# Sprite_Sail_2_Layer.net
KiCad netlist of a schematic drawn in EAGLE
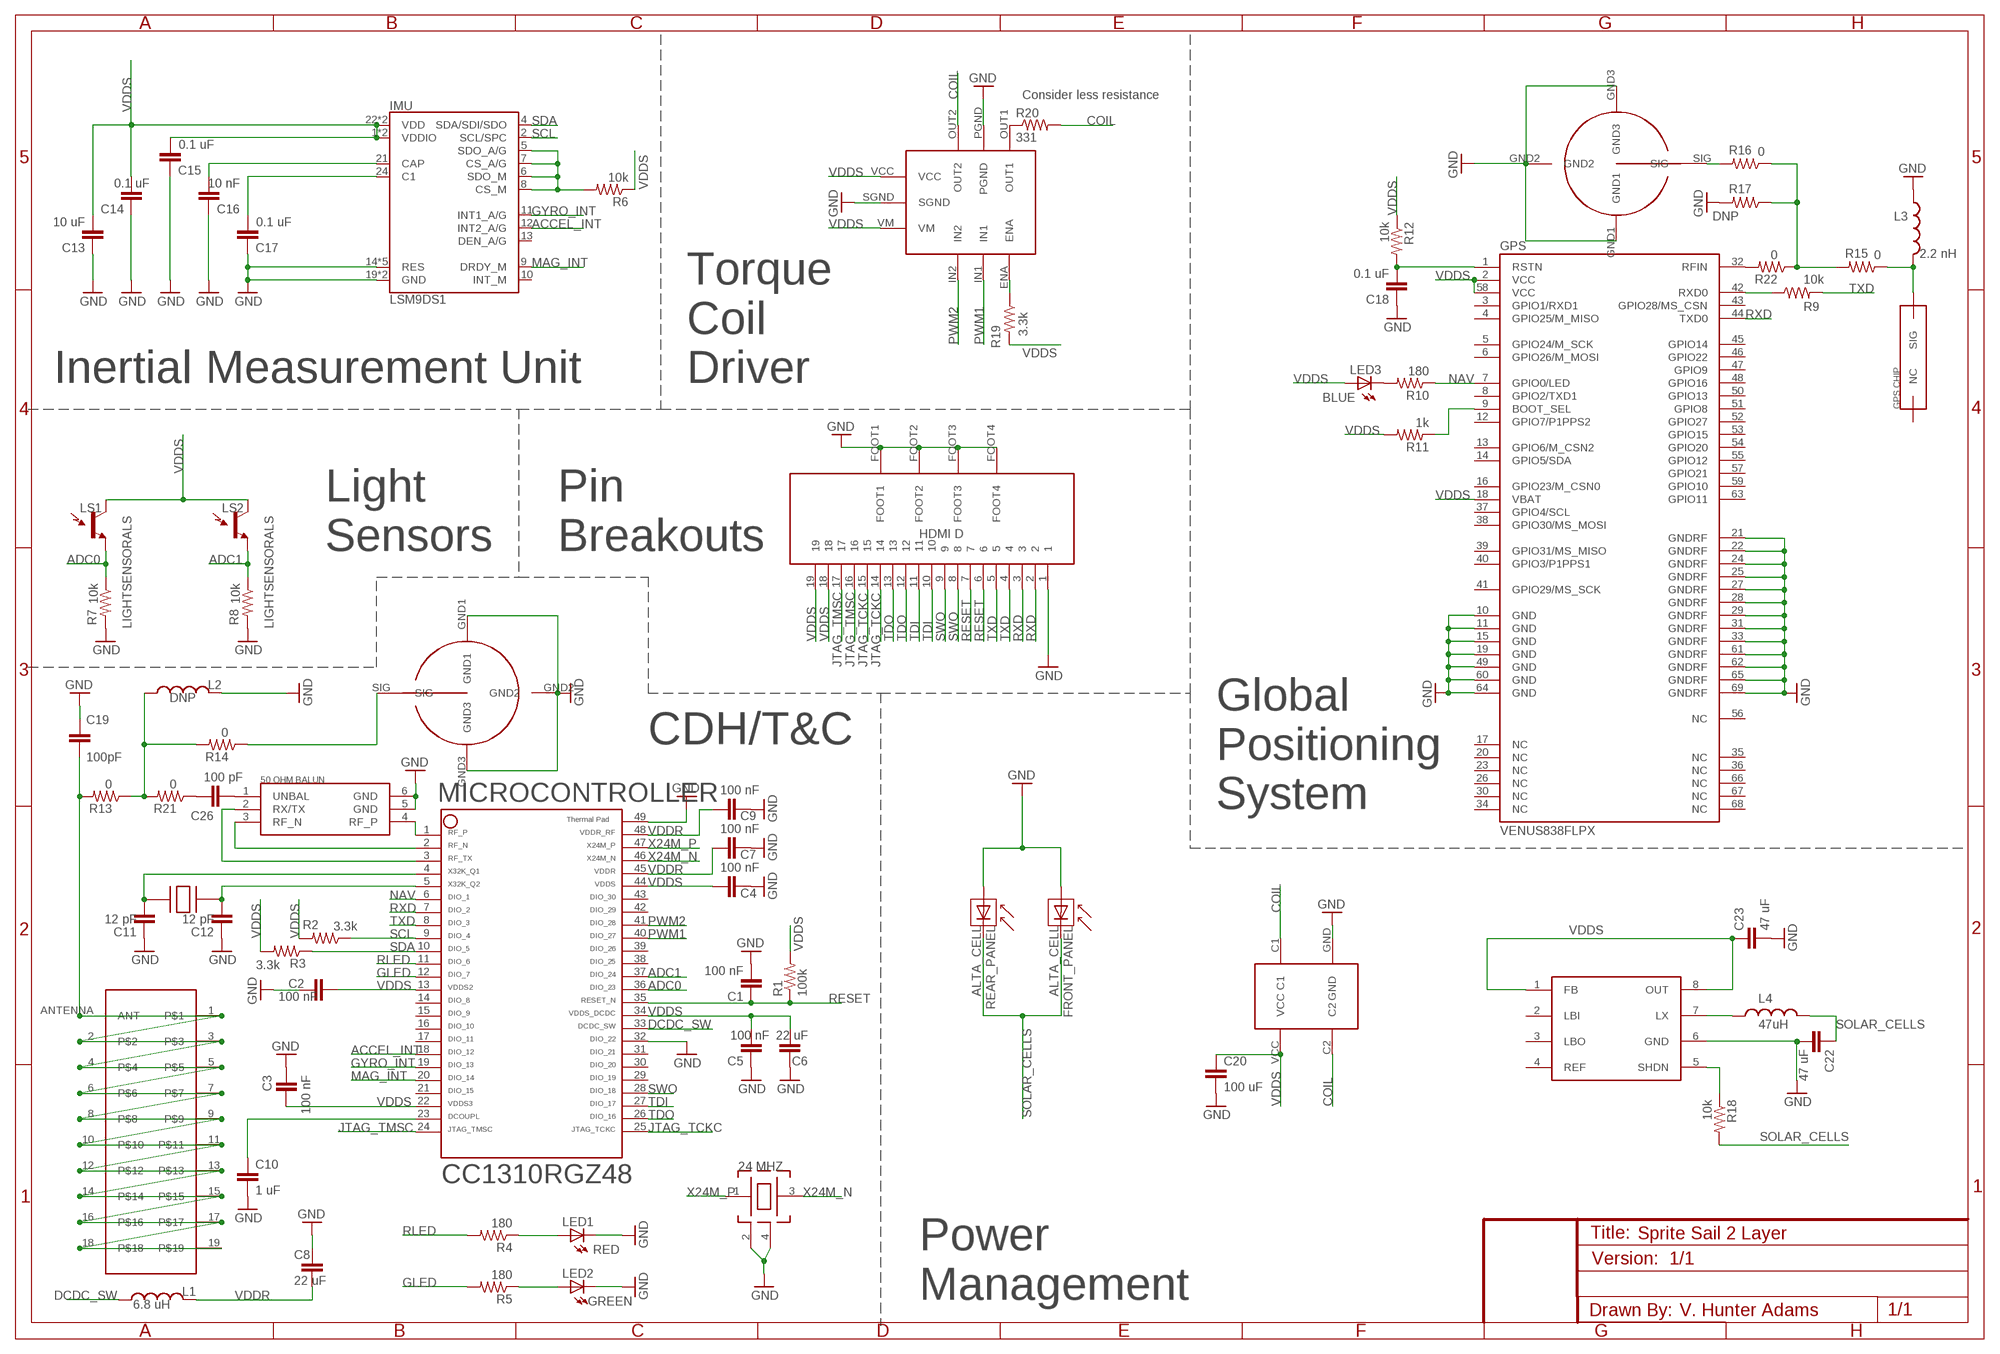
[diagram p0: schematic, sheet 1]

(export (version "E")
  (design (tool "Eeschema 10.0.6"))
  (components
    (comp (ref "32.768")
      (value "FC-135")
      (footprint "eagle-import:FC-135")
      (libsource (lib "eagle-import") (part "FC-135"))
    )
    (comp (ref "BALUN")
      (value "JOHANSON_BALUN")
      (footprint "eagle-import:JOHANSON_BALUN")
      (libsource (lib "eagle-import") (part "JOHANSON_BALUN"))
    )
    (comp (ref "C1")
      (value "100 nF")
      (footprint "eagle-import:0402-CAP")
      (libsource (lib "eagle-import") (part "CAP0402-CAP"))
    )
    (comp (ref "C2")
      (value "100 nF")
      (footprint "eagle-import:0402-CAP")
      (libsource (lib "eagle-import") (part "CAP0402-CAP"))
    )
    (comp (ref "C3")
      (value "100 nF")
      (footprint "eagle-import:0402-CAP")
      (libsource (lib "eagle-import") (part "CAP0402-CAP"))
    )
    (comp (ref "C4")
      (value "100 nF")
      (footprint "eagle-import:0402-CAP")
      (libsource (lib "eagle-import") (part "CAP0402-CAP"))
    )
    (comp (ref "C5")
      (value "100 nF")
      (footprint "eagle-import:0402-CAP")
      (libsource (lib "eagle-import") (part "CAP0402-CAP"))
    )
    (comp (ref "C6")
      (value "22 uF")
      (footprint "eagle-import:0402-CAP")
      (libsource (lib "eagle-import") (part "CAP0402-CAP"))
    )
    (comp (ref "C7")
      (value "100 nF")
      (footprint "eagle-import:0402-CAP")
      (libsource (lib "eagle-import") (part "CAP0402-CAP"))
    )
    (comp (ref "C8")
      (value "22 uF")
      (footprint "eagle-import:0402-CAP")
      (libsource (lib "eagle-import") (part "CAP0402-CAP"))
    )
    (comp (ref "C9")
      (value "100 nF")
      (footprint "eagle-import:0402-CAP")
      (libsource (lib "eagle-import") (part "CAP0402-CAP"))
    )
    (comp (ref "C10")
      (value "1 uF")
      (footprint "eagle-import:0402-CAP")
      (libsource (lib "eagle-import") (part "CAP0402-CAP"))
    )
    (comp (ref "C11")
      (value "12 pF")
      (footprint "eagle-import:0402-CAP")
      (libsource (lib "eagle-import") (part "CAP0402-CAP"))
    )
    (comp (ref "C12")
      (value "12 pF")
      (footprint "eagle-import:0402-CAP")
      (libsource (lib "eagle-import") (part "CAP0402-CAP"))
    )
    (comp (ref "C13")
      (value "10 uF")
      (footprint "eagle-import:0402-CAP")
      (libsource (lib "eagle-import") (part "CAP0402-CAP"))
    )
    (comp (ref "C14")
      (value "0.1 uF")
      (footprint "eagle-import:0402-CAP")
      (libsource (lib "eagle-import") (part "CAP0402-CAP"))
    )
    (comp (ref "C15")
      (value "0.1 uF")
      (footprint "eagle-import:0402-CAP")
      (libsource (lib "eagle-import") (part "CAP0402-CAP"))
    )
    (comp (ref "C16")
      (value "10 nF")
      (footprint "eagle-import:0402-CAP")
      (libsource (lib "eagle-import") (part "CAP0402-CAP"))
    )
    (comp (ref "C17")
      (value "0.1 uF")
      (footprint "eagle-import:0402-CAP")
      (libsource (lib "eagle-import") (part "CAP0402-CAP"))
    )
    (comp (ref "C18")
      (value "0.1 uF")
      (footprint "eagle-import:0402-CAP")
      (libsource (lib "eagle-import") (part "CAP0402-CAP"))
    )
    (comp (ref "C19")
      (value "100pF")
      (footprint "eagle-import:0603-CAP")
      (libsource (lib "eagle-import") (part "CAP0603-CAP"))
    )
    (comp (ref "C20")
      (value "100 uF")
      (footprint "eagle-import:0805")
      (libsource (lib "eagle-import") (part "CAP0805"))
    )
    (comp (ref "C22")
      (value "47 uF")
      (footprint "eagle-import:0805")
      (libsource (lib "eagle-import") (part "CAP0805"))
    )
    (comp (ref "C23")
      (value "47 uF")
      (footprint "eagle-import:0805")
      (libsource (lib "eagle-import") (part "CAP0805"))
    )
    (comp (ref "C26")
      (value "100 pF")
      (footprint "eagle-import:0402-CAP")
      (libsource (lib "eagle-import") (part "CAP0402-CAP"))
    )
    (comp (ref "FRONT_PANEL")
      (value "ALTA_CELL")
      (footprint "eagle-import:ALTA_CELL")
      (libsource (lib "eagle-import") (part "ALTA_CELL"))
    )
    (comp (ref "GPS")
      (value "VENUS838FLPX")
      (footprint "eagle-import:VENUS838FLPX")
      (libsource (lib "eagle-import") (part "VENUS838FLPX"))
    )
    (comp (ref "IMU")
      (value "LSM9DS1")
      (footprint "eagle-import:LGA24-8X4")
      (libsource (lib "eagle-import") (part "LSM9DS1"))
    )
    (comp (ref "L1")
      (value "6.8 uH")
      (footprint "eagle-import:0603")
      (libsource (lib "eagle-import") (part "INDUCTOR0603"))
    )
    (comp (ref "L2")
      (value "DNP")
      (footprint "eagle-import:0603")
      (libsource (lib "eagle-import") (part "INDUCTOR0603"))
    )
    (comp (ref "L3")
      (value "2.2 nH")
      (footprint "eagle-import:0603")
      (libsource (lib "eagle-import") (part "INDUCTOR0603"))
    )
    (comp (ref "L4")
      (value "47uH")
      (footprint "eagle-import:0603")
      (libsource (lib "eagle-import") (part "INDUCTOR0603"))
    )
    (comp (ref "LED1")
      (value "RED")
      (footprint "eagle-import:LED-0603")
      (libsource (lib "eagle-import") (part "LED0603"))
    )
    (comp (ref "LED2")
      (value "GREEN")
      (footprint "eagle-import:LED-0603")
      (libsource (lib "eagle-import") (part "LED0603"))
    )
    (comp (ref "LED3")
      (value "BLUE")
      (footprint "eagle-import:LED-0603")
      (libsource (lib "eagle-import") (part "LED0603"))
    )
    (comp (ref "LS1")
      (value "LIGHTSENSORALS")
      (footprint "eagle-import:ALS-PT19")
      (libsource (lib "eagle-import") (part "LIGHTSENSORALS"))
    )
    (comp (ref "LS2")
      (value "LIGHTSENSORALS")
      (footprint "eagle-import:ALS-PT19")
      (libsource (lib "eagle-import") (part "LIGHTSENSORALS"))
    )
    (comp (ref "MICROCONTROLLER")
      (value "CC1310")
      (footprint "eagle-import:CC1310")
      (libsource (lib "eagle-import") (part "CC1310"))
    )
    (comp (ref "R1")
      (value "100k")
      (footprint "eagle-import:0402-RES")
      (libsource (lib "eagle-import") (part "RESISTOR0402-RES"))
    )
    (comp (ref "R2")
      (value "3.3k")
      (footprint "eagle-import:0402-RES")
      (libsource (lib "eagle-import") (part "RESISTOR0402-RES"))
    )
    (comp (ref "R3")
      (value "3.3k")
      (footprint "eagle-import:0402-RES")
      (libsource (lib "eagle-import") (part "RESISTOR0402-RES"))
    )
    (comp (ref "R4")
      (value "180")
      (footprint "eagle-import:0402-RES")
      (libsource (lib "eagle-import") (part "RESISTOR0402-RES"))
    )
    (comp (ref "R5")
      (value "180")
      (footprint "eagle-import:0402-RES")
      (libsource (lib "eagle-import") (part "RESISTOR0402-RES"))
    )
    (comp (ref "R6")
      (value "10k")
      (footprint "eagle-import:0402-RES")
      (libsource (lib "eagle-import") (part "RESISTOR0402-RES"))
    )
    (comp (ref "R7")
      (value "10k")
      (footprint "eagle-import:0402-RES")
      (libsource (lib "eagle-import") (part "RESISTOR0402-RES"))
    )
    (comp (ref "R8")
      (value "10k")
      (footprint "eagle-import:0402-RES")
      (libsource (lib "eagle-import") (part "RESISTOR0402-RES"))
    )
    (comp (ref "R9")
      (value "10k")
      (footprint "eagle-import:0402-RES")
      (libsource (lib "eagle-import") (part "RESISTOR0402-RES"))
    )
    (comp (ref "R10")
      (value "180")
      (footprint "eagle-import:0402-RES")
      (libsource (lib "eagle-import") (part "RESISTOR0402-RES"))
    )
    (comp (ref "R11")
      (value "1k")
      (footprint "eagle-import:0402-RES")
      (libsource (lib "eagle-import") (part "RESISTOR0402-RES"))
    )
    (comp (ref "R12")
      (value "10k")
      (footprint "eagle-import:0402-RES")
      (libsource (lib "eagle-import") (part "RESISTOR0402-RES"))
    )
    (comp (ref "R13")
      (value "0")
      (footprint "eagle-import:0603-RES")
      (libsource (lib "eagle-import") (part "RESISTOR0603-RES"))
    )
    (comp (ref "R14")
      (value "0")
      (footprint "eagle-import:0603-RES")
      (libsource (lib "eagle-import") (part "RESISTOR0603-RES"))
    )
    (comp (ref "R15")
      (value "0")
      (footprint "eagle-import:0603-RES")
      (libsource (lib "eagle-import") (part "RESISTOR0603-RES"))
    )
    (comp (ref "R16")
      (value "0")
      (footprint "eagle-import:0603-RES")
      (libsource (lib "eagle-import") (part "RESISTOR0603-RES"))
    )
    (comp (ref "R17")
      (value "DNP")
      (footprint "eagle-import:0603-RES")
      (libsource (lib "eagle-import") (part "RESISTOR0603-RES"))
    )
    (comp (ref "R18")
      (value "10k")
      (footprint "eagle-import:0402-RES")
      (libsource (lib "eagle-import") (part "RESISTOR0402-RES"))
    )
    (comp (ref "R19")
      (value "3.3k")
      (footprint "eagle-import:0402-RES")
      (libsource (lib "eagle-import") (part "RESISTOR0402-RES"))
    )
    (comp (ref "R20")
      (value "331")
      (footprint "eagle-import:0402-RES")
      (libsource (lib "eagle-import") (part "RESISTOR0402-RES"))
    )
    (comp (ref "R21")
      (value "0")
      (footprint "eagle-import:0603-RES")
      (libsource (lib "eagle-import") (part "RESISTOR0603-RES"))
    )
    (comp (ref "R22")
      (value "0")
      (footprint "eagle-import:0603-RES")
      (libsource (lib "eagle-import") (part "RESISTOR0603-RES"))
    )
    (comp (ref "REAR_PANEL")
      (value "ALTA_CELL")
      (footprint "eagle-import:ALTA_CELL")
      (libsource (lib "eagle-import") (part "ALTA_CELL"))
    )
    (comp (ref "TSX3225")
      (value "TSX-3225")
      (footprint "eagle-import:TSX-3225")
      (libsource (lib "eagle-import") (part "TSX-3225"))
    )
    (comp (ref "U$2")
      (value "LV8417CS")
      (footprint "eagle-import:LV8417CS")
      (libsource (lib "eagle-import") (part "LV8417CS"))
    )
    (comp (ref "U$3")
      (value "MM5329-2700")
      (footprint "eagle-import:MM5829-2700")
      (libsource (lib "eagle-import") (part "MM5329-2700"))
    )
    (comp (ref "U$4")
      (value "PANASONIC_RECTIFIER")
      (footprint "eagle-import:PANASONIC_RECTIFIER")
      (libsource (lib "eagle-import") (part "PANASONIC_RECTIFIER"))
    )
    (comp (ref "U$5")
      (value "JOHANSON_GPS_CHIP")
      (footprint "eagle-import:JOHANSON_GPS_CHIP")
      (libsource (lib "eagle-import") (part "JOHANSON_GPS_CHIP"))
    )
    (comp (ref "U$6")
      (value "PCB_ANTENNA")
      (footprint "eagle-import:PCB_ANTENNA")
      (libsource (lib "eagle-import") (part "PCB_ANTENNA"))
    )
    (comp (ref "U$7")
      (value "MM5329-2700")
      (footprint "eagle-import:MM5829-2700")
      (libsource (lib "eagle-import") (part "MM5329-2700"))
    )
    (comp (ref "U$8")
      (value "L6920")
      (footprint "eagle-import:L6920")
      (libsource (lib "eagle-import") (part "L6920"))
    )
    (comp (ref "U$9")
      (value "HDMID")
      (footprint "eagle-import:HDMID")
      (libsource (lib "eagle-import") (part "HDMID"))
    )
  )
  (nets
    (net (code "1") (name "/ACCEL_INT") (class "Default")
      (node (ref "IMU") (pin "12") (pinfunction "INT2_A/G_12") (pintype "bidirectional"))
      (node (ref "MICROCONTROLLER") (pin "18") (pinfunction "18_18") (pintype "bidirectional"))
    )
    (net (code "2") (name "/ADC0") (class "Default")
      (node (ref "LS1") (pin "E") (pinfunction "E1_E") (pintype "passive"))
      (node (ref "MICROCONTROLLER") (pin "36") (pinfunction "36_36") (pintype "bidirectional"))
      (node (ref "R7") (pin "1") (pinfunction "1_1") (pintype "passive"))
    )
    (net (code "3") (name "/ADC1") (class "Default")
      (node (ref "LS2") (pin "E") (pinfunction "E1_E") (pintype "passive"))
      (node (ref "MICROCONTROLLER") (pin "37") (pinfunction "37_37") (pintype "bidirectional"))
      (node (ref "R8") (pin "1") (pinfunction "1_1") (pintype "passive"))
    )
    (net (code "4") (name "/COIL") (class "Default")
      (node (ref "R20") (pin "2") (pinfunction "2_2") (pintype "passive"))
      (node (ref "U$2") (pin "OUT2") (pinfunction "OUT2_OUT2") (pintype "bidirectional"))
      (node (ref "U$4") (pin "C1") (pinfunction "C1_C1") (pintype "bidirectional"))
      (node (ref "U$4") (pin "C2") (pinfunction "C2_C2") (pintype "bidirectional"))
    )
    (net (code "5") (name "/DCDC_SW") (class "Default")
      (node (ref "L1") (pin "1") (pinfunction "1_1") (pintype "passive"))
      (node (ref "MICROCONTROLLER") (pin "33") (pinfunction "33_33") (pintype "power_in"))
    )
    (net (code "6") (name "/GLED") (class "Default")
      (node (ref "MICROCONTROLLER") (pin "12") (pinfunction "12_12") (pintype "bidirectional"))
      (node (ref "R5") (pin "2") (pinfunction "2_2") (pintype "passive"))
    )
    (net (code "7") (name "/GYRO_INT") (class "Default")
      (node (ref "IMU") (pin "11") (pinfunction "INT1_A/G_11") (pintype "bidirectional"))
      (node (ref "MICROCONTROLLER") (pin "19") (pinfunction "19_19") (pintype "bidirectional"))
    )
    (net (code "8") (name "/JTAG_TCKC") (class "Default")
      (node (ref "MICROCONTROLLER") (pin "25") (pinfunction "25_25") (pintype "input"))
      (node (ref "U$9") (pin "14") (pinfunction "14_14") (pintype "bidirectional"))
      (node (ref "U$9") (pin "15") (pinfunction "15_15") (pintype "bidirectional"))
    )
    (net (code "9") (name "/JTAG_TMSC") (class "Default")
      (node (ref "MICROCONTROLLER") (pin "24") (pinfunction "24_24") (pintype "bidirectional"))
      (node (ref "U$9") (pin "16") (pinfunction "16_16") (pintype "bidirectional"))
      (node (ref "U$9") (pin "17") (pinfunction "17_17") (pintype "bidirectional"))
    )
    (net (code "10") (name "/MAG_INT") (class "Default")
      (node (ref "IMU") (pin "9") (pinfunction "DRDY_M_9") (pintype "bidirectional"))
      (node (ref "MICROCONTROLLER") (pin "20") (pinfunction "20_20") (pintype "bidirectional"))
    )
    (net (code "11") (name "/NAV") (class "Default")
      (node (ref "GPS") (pin "7") (pinfunction "GPIO0/LED_7") (pintype "bidirectional"))
      (node (ref "MICROCONTROLLER") (pin "6") (pinfunction "6_6") (pintype "bidirectional"))
      (node (ref "R10") (pin "1") (pinfunction "1_1") (pintype "passive"))
    )
    (net (code "12") (name "/PWM1") (class "Default")
      (node (ref "MICROCONTROLLER") (pin "40") (pinfunction "40_40") (pintype "bidirectional"))
      (node (ref "U$2") (pin "IN1") (pinfunction "IN1_IN1") (pintype "bidirectional"))
    )
    (net (code "13") (name "/PWM2") (class "Default")
      (node (ref "MICROCONTROLLER") (pin "41") (pinfunction "41_41") (pintype "bidirectional"))
      (node (ref "U$2") (pin "IN2") (pinfunction "IN2_IN2") (pintype "bidirectional"))
    )
    (net (code "14") (name "/RESET") (class "Default")
      (node (ref "C1") (pin "1") (pinfunction "1_1") (pintype "passive"))
      (node (ref "MICROCONTROLLER") (pin "35") (pinfunction "35_35") (pintype "input"))
      (node (ref "R1") (pin "1") (pinfunction "1_1") (pintype "passive"))
      (node (ref "U$9") (pin "6") (pinfunction "6_6") (pintype "bidirectional"))
      (node (ref "U$9") (pin "7") (pinfunction "7_7") (pintype "bidirectional"))
    )
    (net (code "15") (name "/RLED") (class "Default")
      (node (ref "MICROCONTROLLER") (pin "11") (pinfunction "11_11") (pintype "bidirectional"))
      (node (ref "R4") (pin "2") (pinfunction "2_2") (pintype "passive"))
    )
    (net (code "16") (name "/RXD") (class "Default")
      (node (ref "GPS") (pin "44") (pinfunction "TXD0_44") (pintype "bidirectional"))
      (node (ref "MICROCONTROLLER") (pin "7") (pinfunction "7_7") (pintype "bidirectional"))
      (node (ref "U$9") (pin "2") (pinfunction "2_2") (pintype "bidirectional"))
      (node (ref "U$9") (pin "3") (pinfunction "3_3") (pintype "bidirectional"))
    )
    (net (code "17") (name "/SCL") (class "Default")
      (node (ref "IMU") (pin "2") (pinfunction "SCL/SPC_2") (pintype "bidirectional"))
      (node (ref "MICROCONTROLLER") (pin "9") (pinfunction "9_9") (pintype "bidirectional"))
      (node (ref "R2") (pin "1") (pinfunction "1_1") (pintype "passive"))
    )
    (net (code "18") (name "/SDA") (class "Default")
      (node (ref "IMU") (pin "4") (pinfunction "SDA/SDI/SDO_4") (pintype "bidirectional"))
      (node (ref "MICROCONTROLLER") (pin "10") (pinfunction "10_10") (pintype "bidirectional"))
      (node (ref "R3") (pin "1") (pinfunction "1_1") (pintype "passive"))
    )
    (net (code "19") (name "/SOLAR_CELLS") (class "Default")
      (node (ref "C22") (pin "1") (pinfunction "1_1") (pintype "passive"))
      (node (ref "FRONT_PANEL") (pin "+") (pinfunction "+_+") (pintype "passive"))
      (node (ref "L4") (pin "2") (pinfunction "2_2") (pintype "passive"))
      (node (ref "R18") (pin "2") (pinfunction "2_2") (pintype "passive"))
      (node (ref "REAR_PANEL") (pin "+") (pinfunction "+_+") (pintype "passive"))
    )
    (net (code "20") (name "/SWO") (class "Default")
      (node (ref "MICROCONTROLLER") (pin "28") (pinfunction "28_28") (pintype "bidirectional"))
      (node (ref "U$9") (pin "8") (pinfunction "8_8") (pintype "bidirectional"))
      (node (ref "U$9") (pin "9") (pinfunction "9_9") (pintype "bidirectional"))
    )
    (net (code "21") (name "/TDI") (class "Default")
      (node (ref "MICROCONTROLLER") (pin "27") (pinfunction "27_27") (pintype "bidirectional"))
      (node (ref "U$9") (pin "10") (pinfunction "10_10") (pintype "bidirectional"))
      (node (ref "U$9") (pin "11") (pinfunction "11_11") (pintype "bidirectional"))
    )
    (net (code "22") (name "/TDO") (class "Default")
      (node (ref "MICROCONTROLLER") (pin "26") (pinfunction "26_26") (pintype "bidirectional"))
      (node (ref "U$9") (pin "12") (pinfunction "12_12") (pintype "bidirectional"))
      (node (ref "U$9") (pin "13") (pinfunction "13_13") (pintype "bidirectional"))
    )
    (net (code "23") (name "/TXD") (class "Default")
      (node (ref "MICROCONTROLLER") (pin "8") (pinfunction "8_8") (pintype "bidirectional"))
      (node (ref "R9") (pin "2") (pinfunction "2_2") (pintype "passive"))
      (node (ref "U$9") (pin "4") (pinfunction "4_4") (pintype "bidirectional"))
      (node (ref "U$9") (pin "5") (pinfunction "5_5") (pintype "bidirectional"))
    )
    (net (code "24") (name "/VDDR") (class "Default")
      (node (ref "C7") (pin "1") (pinfunction "1_1") (pintype "passive"))
      (node (ref "C8") (pin "1") (pinfunction "1_1") (pintype "passive"))
      (node (ref "C9") (pin "1") (pinfunction "1_1") (pintype "passive"))
      (node (ref "L1") (pin "2") (pinfunction "2_2") (pintype "passive"))
      (node (ref "MICROCONTROLLER") (pin "45") (pinfunction "45_45") (pintype "power_in"))
      (node (ref "MICROCONTROLLER") (pin "48") (pinfunction "48_48") (pintype "power_in"))
    )
    (net (code "25") (name "/VDDS") (class "Default")
      (node (ref "C13") (pin "1") (pinfunction "1_1") (pintype "passive"))
      (node (ref "C14") (pin "1") (pinfunction "1_1") (pintype "passive"))
      (node (ref "C15") (pin "1") (pinfunction "1_1") (pintype "passive"))
      (node (ref "C2") (pin "1") (pinfunction "1_1") (pintype "passive"))
      (node (ref "C20") (pin "1") (pinfunction "1_1") (pintype "passive"))
      (node (ref "C23") (pin "1") (pinfunction "1_1") (pintype "passive"))
      (node (ref "C3") (pin "1") (pinfunction "1_1") (pintype "passive"))
      (node (ref "C4") (pin "1") (pinfunction "1_1") (pintype "passive"))
      (node (ref "C5") (pin "1") (pinfunction "1_1") (pintype "passive"))
      (node (ref "C6") (pin "1") (pinfunction "1_1") (pintype "passive"))
      (node (ref "GPS") (pin "18") (pinfunction "VBAT_18") (pintype "bidirectional"))
      (node (ref "GPS") (pin "2") (pinfunction "VCC_2") (pintype "bidirectional"))
      (node (ref "GPS") (pin "58") (pinfunction "VCC_58") (pintype "bidirectional"))
      (node (ref "IMU") (pin "1") (pinfunction "VDDIO_1") (pintype "bidirectional"))
      (node (ref "IMU") (pin "22") (pinfunction "VDD_22") (pintype "bidirectional"))
      (node (ref "IMU") (pin "23") (pinfunction "VDD_23") (pintype "bidirectional"))
      (node (ref "IMU") (pin "3") (pinfunction "VDDIO_3") (pintype "bidirectional"))
      (node (ref "LED3") (pin "A") (pinfunction "A_A") (pintype "passive"))
      (node (ref "LS1") (pin "C") (pinfunction "C1_C") (pintype "passive"))
      (node (ref "LS2") (pin "C") (pinfunction "C1_C") (pintype "passive"))
      (node (ref "MICROCONTROLLER") (pin "13") (pinfunction "13_13") (pintype "bidirectional"))
      (node (ref "MICROCONTROLLER") (pin "22") (pinfunction "22_22") (pintype "power_in"))
      (node (ref "MICROCONTROLLER") (pin "34") (pinfunction "34_34") (pintype "power_in"))
      (node (ref "MICROCONTROLLER") (pin "44") (pinfunction "44_44") (pintype "power_in"))
      (node (ref "R1") (pin "2") (pinfunction "2_2") (pintype "passive"))
      (node (ref "R11") (pin "2") (pinfunction "2_2") (pintype "passive"))
      (node (ref "R12") (pin "1") (pinfunction "1_1") (pintype "passive"))
      (node (ref "R19") (pin "2") (pinfunction "2_2") (pintype "passive"))
      (node (ref "R2") (pin "2") (pinfunction "2_2") (pintype "passive"))
      (node (ref "R3") (pin "2") (pinfunction "2_2") (pintype "passive"))
      (node (ref "R6") (pin "1") (pinfunction "1_1") (pintype "passive"))
      (node (ref "U$2") (pin "VCC") (pinfunction "VCC_VCC") (pintype "bidirectional"))
      (node (ref "U$2") (pin "VM") (pinfunction "VM_VM") (pintype "bidirectional"))
      (node (ref "U$4") (pin "VCC") (pinfunction "VCC_VCC") (pintype "bidirectional"))
      (node (ref "U$8") (pin "1") (pinfunction "FB_1") (pintype "bidirectional"))
      (node (ref "U$8") (pin "8") (pinfunction "OUT_8") (pintype "bidirectional"))
      (node (ref "U$9") (pin "18") (pinfunction "18_18") (pintype "bidirectional"))
      (node (ref "U$9") (pin "19") (pinfunction "19_19") (pintype "bidirectional"))
    )
    (net (code "26") (name "/X24M_N") (class "Default")
      (node (ref "MICROCONTROLLER") (pin "46") (pinfunction "46_46") (pintype "bidirectional"))
      (node (ref "TSX3225") (pin "3") (pinfunction "3_3") (pintype "bidirectional"))
    )
    (net (code "27") (name "/X24M_P") (class "Default")
      (node (ref "MICROCONTROLLER") (pin "47") (pinfunction "47_47") (pintype "input"))
      (node (ref "TSX3225") (pin "1") (pinfunction "1_1") (pintype "bidirectional"))
    )
    (net (code "28") (name "GND") (class "Default")
      (node (ref "BALUN") (pin "5") (pinfunction "GND_5") (pintype "bidirectional"))
      (node (ref "BALUN") (pin "6") (pinfunction "GND_6") (pintype "bidirectional"))
      (node (ref "C1") (pin "2") (pinfunction "2_2") (pintype "passive"))
      (node (ref "C10") (pin "2") (pinfunction "2_2") (pintype "passive"))
      (node (ref "C11") (pin "2") (pinfunction "2_2") (pintype "passive"))
      (node (ref "C12") (pin "2") (pinfunction "2_2") (pintype "passive"))
      (node (ref "C13") (pin "2") (pinfunction "2_2") (pintype "passive"))
      (node (ref "C14") (pin "2") (pinfunction "2_2") (pintype "passive"))
      (node (ref "C15") (pin "2") (pinfunction "2_2") (pintype "passive"))
      (node (ref "C16") (pin "2") (pinfunction "2_2") (pintype "passive"))
      (node (ref "C17") (pin "2") (pinfunction "2_2") (pintype "passive"))
      (node (ref "C18") (pin "2") (pinfunction "2_2") (pintype "passive"))
      (node (ref "C19") (pin "1") (pinfunction "1_1") (pintype "passive"))
      (node (ref "C2") (pin "2") (pinfunction "2_2") (pintype "passive"))
      (node (ref "C20") (pin "2") (pinfunction "2_2") (pintype "passive"))
      (node (ref "C22") (pin "2") (pinfunction "2_2") (pintype "passive"))
      (node (ref "C23") (pin "2") (pinfunction "2_2") (pintype "passive"))
      (node (ref "C3") (pin "2") (pinfunction "2_2") (pintype "passive"))
      (node (ref "C4") (pin "2") (pinfunction "2_2") (pintype "passive"))
      (node (ref "C5") (pin "2") (pinfunction "2_2") (pintype "passive"))
      (node (ref "C6") (pin "2") (pinfunction "2_2") (pintype "passive"))
      (node (ref "C7") (pin "2") (pinfunction "2_2") (pintype "passive"))
      (node (ref "C8") (pin "2") (pinfunction "2_2") (pintype "passive"))
      (node (ref "C9") (pin "2") (pinfunction "2_2") (pintype "passive"))
      (node (ref "FRONT_PANEL") (pin "-") (pinfunction "-_-") (pintype "passive"))
      (node (ref "GPS") (pin "10") (pinfunction "GND_10") (pintype "bidirectional"))
      (node (ref "GPS") (pin "11") (pinfunction "GND_11") (pintype "bidirectional"))
      (node (ref "GPS") (pin "15") (pinfunction "GND_15") (pintype "bidirectional"))
      (node (ref "GPS") (pin "19") (pinfunction "GND_19") (pintype "bidirectional"))
      (node (ref "GPS") (pin "21") (pinfunction "GNDRF_21") (pintype "bidirectional"))
      (node (ref "GPS") (pin "22") (pinfunction "GNDRF_22") (pintype "bidirectional"))
      (node (ref "GPS") (pin "24") (pinfunction "GNDRF_24") (pintype "bidirectional"))
      (node (ref "GPS") (pin "25") (pinfunction "GNDRF_25") (pintype "bidirectional"))
      (node (ref "GPS") (pin "27") (pinfunction "GNDRF_27") (pintype "bidirectional"))
      (node (ref "GPS") (pin "28") (pinfunction "GNDRF_28") (pintype "bidirectional"))
      (node (ref "GPS") (pin "29") (pinfunction "GNDRF_29") (pintype "bidirectional"))
      (node (ref "GPS") (pin "31") (pinfunction "GNDRF_31") (pintype "bidirectional"))
      (node (ref "GPS") (pin "33") (pinfunction "GNDRF_33") (pintype "bidirectional"))
      (node (ref "GPS") (pin "49") (pinfunction "GND_49") (pintype "bidirectional"))
      (node (ref "GPS") (pin "60") (pinfunction "GND_60") (pintype "bidirectional"))
      (node (ref "GPS") (pin "61") (pinfunction "GNDRF_61") (pintype "bidirectional"))
      (node (ref "GPS") (pin "62") (pinfunction "GNDRF_62") (pintype "bidirectional"))
      (node (ref "GPS") (pin "64") (pinfunction "GND_64") (pintype "bidirectional"))
      (node (ref "GPS") (pin "65") (pinfunction "GNDRF_65") (pintype "bidirectional"))
      (node (ref "GPS") (pin "69") (pinfunction "GNDRF_69") (pintype "bidirectional"))
      (node (ref "IMU") (pin "14") (pinfunction "RES_14") (pintype "bidirectional"))
      (node (ref "IMU") (pin "15") (pinfunction "RES_15") (pintype "bidirectional"))
      (node (ref "IMU") (pin "16") (pinfunction "RES_16") (pintype "bidirectional"))
      (node (ref "IMU") (pin "17") (pinfunction "RES_17") (pintype "bidirectional"))
      (node (ref "IMU") (pin "18") (pinfunction "RES_18") (pintype "bidirectional"))
      (node (ref "IMU") (pin "19") (pinfunction "GND_19") (pintype "bidirectional"))
      (node (ref "IMU") (pin "20") (pinfunction "GND_20") (pintype "bidirectional"))
      (node (ref "L2") (pin "2") (pinfunction "2_2") (pintype "passive"))
      (node (ref "L3") (pin "1") (pinfunction "1_1") (pintype "passive"))
      (node (ref "LED1") (pin "C") (pinfunction "C_C") (pintype "passive"))
      (node (ref "LED2") (pin "C") (pinfunction "C_C") (pintype "passive"))
      (node (ref "MICROCONTROLLER") (pin "32") (pinfunction "32_32") (pintype "bidirectional"))
      (node (ref "MICROCONTROLLER") (pin "49") (pinfunction "49_49") (pintype "input"))
      (node (ref "R17") (pin "2") (pinfunction "2_2") (pintype "passive"))
      (node (ref "R7") (pin "2") (pinfunction "2_2") (pintype "passive"))
      (node (ref "R8") (pin "2") (pinfunction "2_2") (pintype "passive"))
      (node (ref "REAR_PANEL") (pin "-") (pinfunction "-_-") (pintype "passive"))
      (node (ref "TSX3225") (pin "2") (pinfunction "2_2") (pintype "bidirectional"))
      (node (ref "TSX3225") (pin "4") (pinfunction "4_4") (pintype "bidirectional"))
      (node (ref "U$2") (pin "PGND") (pinfunction "PGND_PGND") (pintype "bidirectional"))
      (node (ref "U$2") (pin "SGND") (pinfunction "SGND_SGND") (pintype "bidirectional"))
      (node (ref "U$3") (pin "GND1") (pinfunction "GND1_GND1") (pintype "bidirectional"))
      (node (ref "U$3") (pin "GND2") (pinfunction "GND2_GND2") (pintype "bidirectional"))
      (node (ref "U$3") (pin "GND3") (pinfunction "GND3_GND3") (pintype "bidirectional"))
      (node (ref "U$4") (pin "GND") (pinfunction "GND_GND") (pintype "bidirectional"))
      (node (ref "U$7") (pin "GND1") (pinfunction "GND1_GND1") (pintype "bidirectional"))
      (node (ref "U$7") (pin "GND2") (pinfunction "GND2_GND2") (pintype "bidirectional"))
      (node (ref "U$7") (pin "GND3") (pinfunction "GND3_GND3") (pintype "bidirectional"))
      (node (ref "U$8") (pin "6") (pinfunction "GND_6") (pintype "bidirectional"))
      (node (ref "U$9") (pin "1") (pinfunction "1_1") (pintype "bidirectional"))
      (node (ref "U$9") (pin "FOOT1") (pinfunction "FOOT1_FOOT1") (pintype "bidirectional"))
      (node (ref "U$9") (pin "FOOT2") (pinfunction "FOOT2_FOOT2") (pintype "bidirectional"))
      (node (ref "U$9") (pin "FOOT3") (pinfunction "FOOT3_FOOT3") (pintype "bidirectional"))
      (node (ref "U$9") (pin "FOOT4") (pinfunction "FOOT4_FOOT4") (pintype "bidirectional"))
    )
    (net (code "29") (name "Net-(32.768-PadP1)") (class "Default")
      (node (ref "32.768") (pin "P1") (pinfunction "P1_P1") (pintype "bidirectional"))
      (node (ref "C12") (pin "1") (pinfunction "1_1") (pintype "passive"))
      (node (ref "MICROCONTROLLER") (pin "5") (pinfunction "5_5") (pintype "bidirectional"))
    )
    (net (code "30") (name "Net-(32.768-PadP2)") (class "Default")
      (node (ref "32.768") (pin "P2") (pinfunction "P2_P2") (pintype "bidirectional"))
      (node (ref "C11") (pin "1") (pinfunction "1_1") (pintype "passive"))
      (node (ref "MICROCONTROLLER") (pin "4") (pinfunction "4_4") (pintype "bidirectional"))
    )
    (net (code "31") (name "Net-(BALUN-RF_N)") (class "Default")
      (node (ref "BALUN") (pin "3") (pinfunction "RF_N_3") (pintype "bidirectional"))
      (node (ref "MICROCONTROLLER") (pin "2") (pinfunction "2_2") (pintype "bidirectional"))
    )
    (net (code "32") (name "Net-(BALUN-RF_P)") (class "Default")
      (node (ref "BALUN") (pin "4") (pinfunction "RF_P_4") (pintype "bidirectional"))
      (node (ref "MICROCONTROLLER") (pin "1") (pinfunction "1_1") (pintype "bidirectional"))
    )
    (net (code "33") (name "Net-(BALUN-RX{slash}TX)") (class "Default")
      (node (ref "BALUN") (pin "2") (pinfunction "RX/TX_2") (pintype "bidirectional"))
      (node (ref "MICROCONTROLLER") (pin "3") (pinfunction "3_3") (pintype "bidirectional"))
    )
    (net (code "34") (name "Net-(BALUN-UNBAL)") (class "Default")
      (node (ref "BALUN") (pin "1") (pinfunction "UNBAL_1") (pintype "bidirectional"))
      (node (ref "C26") (pin "2") (pinfunction "2_2") (pintype "passive"))
    )
    (net (code "35") (name "Net-(C10-Pad1)") (class "Default")
      (node (ref "C10") (pin "1") (pinfunction "1_1") (pintype "passive"))
      (node (ref "MICROCONTROLLER") (pin "23") (pinfunction "23_23") (pintype "bidirectional"))
    )
    (net (code "36") (name "Net-(C26-Pad1)") (class "Default")
      (node (ref "C26") (pin "1") (pinfunction "1_1") (pintype "passive"))
      (node (ref "R21") (pin "1") (pinfunction "1_1") (pintype "passive"))
    )
    (net (code "37") (name "Net-(GPS-BOOT_SEL)") (class "Default")
      (node (ref "GPS") (pin "9") (pinfunction "BOOT_SEL_9") (pintype "bidirectional"))
      (node (ref "R11") (pin "1") (pinfunction "1_1") (pintype "passive"))
    )
    (net (code "38") (name "Net-(GPS-RFIN)") (class "Default")
      (node (ref "GPS") (pin "32") (pinfunction "RFIN_32") (pintype "bidirectional"))
      (node (ref "R22") (pin "2") (pinfunction "2_2") (pintype "passive"))
    )
    (net (code "39") (name "Net-(GPS-RSTN)") (class "Default")
      (node (ref "C18") (pin "1") (pinfunction "1_1") (pintype "passive"))
      (node (ref "GPS") (pin "1") (pinfunction "RSTN_1") (pintype "bidirectional"))
      (node (ref "R12") (pin "2") (pinfunction "2_2") (pintype "passive"))
    )
    (net (code "40") (name "Net-(GPS-RXD0)") (class "Default")
      (node (ref "GPS") (pin "42") (pinfunction "RXD0_42") (pintype "bidirectional"))
      (node (ref "R9") (pin "1") (pinfunction "1_1") (pintype "passive"))
    )
    (net (code "41") (name "Net-(IMU-C1)") (class "Default")
      (node (ref "C17") (pin "1") (pinfunction "1_1") (pintype "passive"))
      (node (ref "IMU") (pin "24") (pinfunction "C1_24") (pintype "bidirectional"))
    )
    (net (code "42") (name "Net-(IMU-CAP)") (class "Default")
      (node (ref "C16") (pin "1") (pinfunction "1_1") (pintype "passive"))
      (node (ref "IMU") (pin "21") (pinfunction "CAP_21") (pintype "bidirectional"))
    )
    (net (code "43") (name "Net-(IMU-CS_A{slash}G)") (class "Default")
      (node (ref "IMU") (pin "5") (pinfunction "SDO_A/G_5") (pintype "bidirectional"))
      (node (ref "IMU") (pin "6") (pinfunction "SDO_M_6") (pintype "bidirectional"))
      (node (ref "IMU") (pin "7") (pinfunction "CS_A/G_7") (pintype "bidirectional"))
      (node (ref "IMU") (pin "8") (pinfunction "CS_M_8") (pintype "bidirectional"))
      (node (ref "R6") (pin "2") (pinfunction "2_2") (pintype "passive"))
    )
    (net (code "44") (name "Net-(L2-Pad1)") (class "Default")
      (node (ref "L2") (pin "1") (pinfunction "1_1") (pintype "passive"))
      (node (ref "R13") (pin "1") (pinfunction "1_1") (pintype "passive"))
      (node (ref "R14") (pin "2") (pinfunction "2_2") (pintype "passive"))
      (node (ref "R21") (pin "2") (pinfunction "2_2") (pintype "passive"))
    )
    (net (code "45") (name "Net-(L3-Pad2)") (class "Default")
      (node (ref "L3") (pin "2") (pinfunction "2_2") (pintype "passive"))
      (node (ref "R15") (pin "1") (pinfunction "1_1") (pintype "passive"))
      (node (ref "U$5") (pin "SIG") (pinfunction "SIG_SIG") (pintype "bidirectional"))
    )
    (net (code "46") (name "Net-(LED1-PadA)") (class "Default")
      (node (ref "LED1") (pin "A") (pinfunction "A_A") (pintype "passive"))
      (node (ref "R4") (pin "1") (pinfunction "1_1") (pintype "passive"))
    )
    (net (code "47") (name "Net-(LED2-PadA)") (class "Default")
      (node (ref "LED2") (pin "A") (pinfunction "A_A") (pintype "passive"))
      (node (ref "R5") (pin "1") (pinfunction "1_1") (pintype "passive"))
    )
    (net (code "48") (name "Net-(LED3-PadC)") (class "Default")
      (node (ref "LED3") (pin "C") (pinfunction "C_C") (pintype "passive"))
      (node (ref "R10") (pin "2") (pinfunction "2_2") (pintype "passive"))
    )
    (net (code "49") (name "Net-(R14-Pad1)") (class "Default")
      (node (ref "R14") (pin "1") (pinfunction "1_1") (pintype "passive"))
      (node (ref "U$3") (pin "SIG") (pinfunction "SIG_SIG") (pintype "bidirectional"))
    )
    (net (code "50") (name "Net-(R15-Pad2)") (class "Default")
      (node (ref "R15") (pin "2") (pinfunction "2_2") (pintype "passive"))
      (node (ref "R16") (pin "1") (pinfunction "1_1") (pintype "passive"))
      (node (ref "R17") (pin "1") (pinfunction "1_1") (pintype "passive"))
      (node (ref "R22") (pin "1") (pinfunction "1_1") (pintype "passive"))
    )
    (net (code "51") (name "Net-(R16-Pad2)") (class "Default")
      (node (ref "R16") (pin "2") (pinfunction "2_2") (pintype "passive"))
      (node (ref "U$7") (pin "SIG") (pinfunction "SIG_SIG") (pintype "bidirectional"))
    )
    (net (code "52") (name "Net-(R19-Pad1)") (class "Default")
      (node (ref "R19") (pin "1") (pinfunction "1_1") (pintype "passive"))
      (node (ref "U$2") (pin "ENA") (pinfunction "ENA_ENA") (pintype "bidirectional"))
    )
    (net (code "53") (name "Net-(R20-Pad1)") (class "Default")
      (node (ref "R20") (pin "1") (pinfunction "1_1") (pintype "passive"))
      (node (ref "U$2") (pin "OUT1") (pinfunction "OUT1_OUT1") (pintype "bidirectional"))
    )
    (net (code "54") (name "Net-(U$6-ANT)") (class "Default")
      (node (ref "C19") (pin "2") (pinfunction "2_2") (pintype "passive"))
      (node (ref "R13") (pin "2") (pinfunction "2_2") (pintype "passive"))
      (node (ref "U$6") (pin "1") (pinfunction "P$1_1") (pintype "bidirectional"))
      (node (ref "U$6") (pin "10") (pinfunction "P$10_10") (pintype "bidirectional"))
      (node (ref "U$6") (pin "11") (pinfunction "P$11_11") (pintype "bidirectional"))
      (node (ref "U$6") (pin "12") (pinfunction "P$12_12") (pintype "bidirectional"))
      (node (ref "U$6") (pin "13") (pinfunction "P$13_13") (pintype "bidirectional"))
      (node (ref "U$6") (pin "14") (pinfunction "P$14_14") (pintype "bidirectional"))
      (node (ref "U$6") (pin "15") (pinfunction "P$15_15") (pintype "bidirectional"))
      (node (ref "U$6") (pin "16") (pinfunction "P$16_16") (pintype "bidirectional"))
      (node (ref "U$6") (pin "17") (pinfunction "P$17_17") (pintype "bidirectional"))
      (node (ref "U$6") (pin "18") (pinfunction "P$18_18") (pintype "bidirectional"))
      (node (ref "U$6") (pin "19") (pinfunction "P$19_19") (pintype "bidirectional"))
      (node (ref "U$6") (pin "2") (pinfunction "P$2_2") (pintype "bidirectional"))
      (node (ref "U$6") (pin "3") (pinfunction "P$3_3") (pintype "bidirectional"))
      (node (ref "U$6") (pin "4") (pinfunction "P$4_4") (pintype "bidirectional"))
      (node (ref "U$6") (pin "5") (pinfunction "P$5_5") (pintype "bidirectional"))
      (node (ref "U$6") (pin "6") (pinfunction "P$6_6") (pintype "bidirectional"))
      (node (ref "U$6") (pin "7") (pinfunction "P$7_7") (pintype "bidirectional"))
      (node (ref "U$6") (pin "8") (pinfunction "P$8_8") (pintype "bidirectional"))
      (node (ref "U$6") (pin "9") (pinfunction "P$9_9") (pintype "bidirectional"))
      (node (ref "U$6") (pin "ANTENNA") (pinfunction "ANT_ANTENNA") (pintype "bidirectional"))
    )
    (net (code "55") (name "Net-(U$8-LX)") (class "Default")
      (node (ref "L4") (pin "1") (pinfunction "1_1") (pintype "passive"))
      (node (ref "U$8") (pin "7") (pinfunction "LX_7") (pintype "bidirectional"))
    )
    (net (code "56") (name "Net-(U$8-SHDN)") (class "Default")
      (node (ref "R18") (pin "1") (pinfunction "1_1") (pintype "passive"))
      (node (ref "U$8") (pin "5") (pinfunction "SHDN_5") (pintype "bidirectional"))
    )
    (net (code "57") (name "unconnected-(GPS-GPIO1{slash}RXD1-Pad3)") (class "Default")
      (node (ref "GPS") (pin "3") (pinfunction "GPIO1/RXD1_3") (pintype "bidirectional"))
    )
    (net (code "58") (name "unconnected-(GPS-GPIO2{slash}TXD1-Pad8)") (class "Default")
      (node (ref "GPS") (pin "8") (pinfunction "GPIO2/TXD1_8") (pintype "bidirectional"))
    )
    (net (code "59") (name "unconnected-(GPS-GPIO3{slash}P1PPS1-Pad40)") (class "Default")
      (node (ref "GPS") (pin "40") (pinfunction "GPIO3/P1PPS1_40") (pintype "bidirectional"))
    )
    (net (code "60") (name "unconnected-(GPS-GPIO4{slash}SCL-Pad37)") (class "Default")
      (node (ref "GPS") (pin "37") (pinfunction "GPIO4/SCL_37") (pintype "bidirectional"))
    )
    (net (code "61") (name "unconnected-(GPS-GPIO5{slash}SDA-Pad14)") (class "Default")
      (node (ref "GPS") (pin "14") (pinfunction "GPIO5/SDA_14") (pintype "bidirectional"))
    )
    (net (code "62") (name "unconnected-(GPS-GPIO6{slash}M_CSN2-Pad13)") (class "Default")
      (node (ref "GPS") (pin "13") (pinfunction "GPIO6/M_CSN2_13") (pintype "bidirectional"))
    )
    (net (code "63") (name "unconnected-(GPS-GPIO7{slash}P1PPS2-Pad12)") (class "Default")
      (node (ref "GPS") (pin "12") (pinfunction "GPIO7/P1PPS2_12") (pintype "bidirectional"))
    )
    (net (code "64") (name "unconnected-(GPS-GPIO8-Pad51)") (class "Default")
      (node (ref "GPS") (pin "51") (pinfunction "GPIO8_51") (pintype "bidirectional"))
    )
    (net (code "65") (name "unconnected-(GPS-GPIO9-Pad47)") (class "Default")
      (node (ref "GPS") (pin "47") (pinfunction "GPIO9_47") (pintype "bidirectional"))
    )
    (net (code "66") (name "unconnected-(GPS-GPIO10-Pad59)") (class "Default")
      (node (ref "GPS") (pin "59") (pinfunction "GPIO10_59") (pintype "bidirectional"))
    )
    (net (code "67") (name "unconnected-(GPS-GPIO11-Pad63)") (class "Default")
      (node (ref "GPS") (pin "63") (pinfunction "GPIO11_63") (pintype "bidirectional"))
    )
    (net (code "68") (name "unconnected-(GPS-GPIO12-Pad55)") (class "Default")
      (node (ref "GPS") (pin "55") (pinfunction "GPIO12_55") (pintype "bidirectional"))
    )
    (net (code "69") (name "unconnected-(GPS-GPIO13-Pad50)") (class "Default")
      (node (ref "GPS") (pin "50") (pinfunction "GPIO13_50") (pintype "bidirectional"))
    )
    (net (code "70") (name "unconnected-(GPS-GPIO14-Pad45)") (class "Default")
      (node (ref "GPS") (pin "45") (pinfunction "GPIO14_45") (pintype "bidirectional"))
    )
    (net (code "71") (name "unconnected-(GPS-GPIO15-Pad53)") (class "Default")
      (node (ref "GPS") (pin "53") (pinfunction "GPIO15_53") (pintype "bidirectional"))
    )
    (net (code "72") (name "unconnected-(GPS-GPIO16-Pad48)") (class "Default")
      (node (ref "GPS") (pin "48") (pinfunction "GPIO16_48") (pintype "bidirectional"))
    )
    (net (code "73") (name "unconnected-(GPS-GPIO20-Pad54)") (class "Default")
      (node (ref "GPS") (pin "54") (pinfunction "GPIO20_54") (pintype "bidirectional"))
    )
    (net (code "74") (name "unconnected-(GPS-GPIO21-Pad57)") (class "Default")
      (node (ref "GPS") (pin "57") (pinfunction "GPIO21_57") (pintype "bidirectional"))
    )
    (net (code "75") (name "unconnected-(GPS-GPIO22-Pad46)") (class "Default")
      (node (ref "GPS") (pin "46") (pinfunction "GPIO22_46") (pintype "bidirectional"))
    )
    (net (code "76") (name "unconnected-(GPS-GPIO23{slash}M_CSN0-Pad16)") (class "Default")
      (node (ref "GPS") (pin "16") (pinfunction "GPIO23/M_CSN0_16") (pintype "bidirectional"))
    )
    (net (code "77") (name "unconnected-(GPS-GPIO24{slash}M_SCK-Pad5)") (class "Default")
      (node (ref "GPS") (pin "5") (pinfunction "GPIO24/M_SCK_5") (pintype "bidirectional"))
    )
    (net (code "78") (name "unconnected-(GPS-GPIO25{slash}M_MISO-Pad4)") (class "Default")
      (node (ref "GPS") (pin "4") (pinfunction "GPIO25/M_MISO_4") (pintype "bidirectional"))
    )
    (net (code "79") (name "unconnected-(GPS-GPIO26{slash}M_MOSI-Pad6)") (class "Default")
      (node (ref "GPS") (pin "6") (pinfunction "GPIO26/M_MOSI_6") (pintype "bidirectional"))
    )
    (net (code "80") (name "unconnected-(GPS-GPIO27-Pad52)") (class "Default")
      (node (ref "GPS") (pin "52") (pinfunction "GPIO27_52") (pintype "bidirectional"))
    )
    (net (code "81") (name "unconnected-(GPS-GPIO28{slash}MS_CSN-Pad43)") (class "Default")
      (node (ref "GPS") (pin "43") (pinfunction "GPIO28/MS_CSN_43") (pintype "bidirectional"))
    )
    (net (code "82") (name "unconnected-(GPS-GPIO29{slash}MS_SCK-Pad41)") (class "Default")
      (node (ref "GPS") (pin "41") (pinfunction "GPIO29/MS_SCK_41") (pintype "bidirectional"))
    )
    (net (code "83") (name "unconnected-(GPS-GPIO30{slash}MS_MOSI-Pad38)") (class "Default")
      (node (ref "GPS") (pin "38") (pinfunction "GPIO30/MS_MOSI_38") (pintype "bidirectional"))
    )
    (net (code "84") (name "unconnected-(GPS-GPIO31{slash}MS_MISO-Pad39)") (class "Default")
      (node (ref "GPS") (pin "39") (pinfunction "GPIO31/MS_MISO_39") (pintype "bidirectional"))
    )
    (net (code "85") (name "unconnected-(GPS-NC-Pad17)") (class "Default")
      (node (ref "GPS") (pin "17") (pinfunction "NC_17") (pintype "bidirectional"))
    )
    (net (code "86") (name "unconnected-(GPS-NC-Pad20)") (class "Default")
      (node (ref "GPS") (pin "20") (pinfunction "NC_20") (pintype "bidirectional"))
    )
    (net (code "87") (name "unconnected-(GPS-NC-Pad23)") (class "Default")
      (node (ref "GPS") (pin "23") (pinfunction "NC_23") (pintype "bidirectional"))
    )
    (net (code "88") (name "unconnected-(GPS-NC-Pad26)") (class "Default")
      (node (ref "GPS") (pin "26") (pinfunction "NC_26") (pintype "bidirectional"))
    )
    (net (code "89") (name "unconnected-(GPS-NC-Pad30)") (class "Default")
      (node (ref "GPS") (pin "30") (pinfunction "NC_30") (pintype "bidirectional"))
    )
    (net (code "90") (name "unconnected-(GPS-NC-Pad34)") (class "Default")
      (node (ref "GPS") (pin "34") (pinfunction "NC_34") (pintype "bidirectional"))
    )
    (net (code "91") (name "unconnected-(GPS-NC-Pad35)") (class "Default")
      (node (ref "GPS") (pin "35") (pinfunction "NC_35") (pintype "bidirectional"))
    )
    (net (code "92") (name "unconnected-(GPS-NC-Pad36)") (class "Default")
      (node (ref "GPS") (pin "36") (pinfunction "NC_36") (pintype "bidirectional"))
    )
    (net (code "93") (name "unconnected-(GPS-NC-Pad56)") (class "Default")
      (node (ref "GPS") (pin "56") (pinfunction "NC_56") (pintype "bidirectional"))
    )
    (net (code "94") (name "unconnected-(GPS-NC-Pad66)") (class "Default")
      (node (ref "GPS") (pin "66") (pinfunction "NC_66") (pintype "bidirectional"))
    )
    (net (code "95") (name "unconnected-(GPS-NC-Pad67)") (class "Default")
      (node (ref "GPS") (pin "67") (pinfunction "NC_67") (pintype "bidirectional"))
    )
    (net (code "96") (name "unconnected-(GPS-NC-Pad68)") (class "Default")
      (node (ref "GPS") (pin "68") (pinfunction "NC_68") (pintype "bidirectional"))
    )
    (net (code "97") (name "unconnected-(IMU-DEN_A{slash}G-Pad13)") (class "Default")
      (node (ref "IMU") (pin "13") (pinfunction "DEN_A/G_13") (pintype "bidirectional"))
    )
    (net (code "98") (name "unconnected-(IMU-INT_M-Pad10)") (class "Default")
      (node (ref "IMU") (pin "10") (pinfunction "INT_M_10") (pintype "bidirectional"))
    )
    (net (code "99") (name "unconnected-(MICROCONTROLLER-Pad14)") (class "Default")
      (node (ref "MICROCONTROLLER") (pin "14") (pinfunction "14_14") (pintype "bidirectional"))
    )
    (net (code "100") (name "unconnected-(MICROCONTROLLER-Pad15)") (class "Default")
      (node (ref "MICROCONTROLLER") (pin "15") (pinfunction "15_15") (pintype "bidirectional"))
    )
    (net (code "101") (name "unconnected-(MICROCONTROLLER-Pad16)") (class "Default")
      (node (ref "MICROCONTROLLER") (pin "16") (pinfunction "16_16") (pintype "bidirectional"))
    )
    (net (code "102") (name "unconnected-(MICROCONTROLLER-Pad17)") (class "Default")
      (node (ref "MICROCONTROLLER") (pin "17") (pinfunction "17_17") (pintype "bidirectional"))
    )
    (net (code "103") (name "unconnected-(MICROCONTROLLER-Pad21)") (class "Default")
      (node (ref "MICROCONTROLLER") (pin "21") (pinfunction "21_21") (pintype "bidirectional"))
    )
    (net (code "104") (name "unconnected-(MICROCONTROLLER-Pad29)") (class "Default")
      (node (ref "MICROCONTROLLER") (pin "29") (pinfunction "29_29") (pintype "bidirectional"))
    )
    (net (code "105") (name "unconnected-(MICROCONTROLLER-Pad30)") (class "Default")
      (node (ref "MICROCONTROLLER") (pin "30") (pinfunction "30_30") (pintype "bidirectional"))
    )
    (net (code "106") (name "unconnected-(MICROCONTROLLER-Pad31)") (class "Default")
      (node (ref "MICROCONTROLLER") (pin "31") (pinfunction "31_31") (pintype "bidirectional"))
    )
    (net (code "107") (name "unconnected-(MICROCONTROLLER-Pad38)") (class "Default")
      (node (ref "MICROCONTROLLER") (pin "38") (pinfunction "38_38") (pintype "bidirectional"))
    )
    (net (code "108") (name "unconnected-(MICROCONTROLLER-Pad39)") (class "Default")
      (node (ref "MICROCONTROLLER") (pin "39") (pinfunction "39_39") (pintype "input"))
    )
    (net (code "109") (name "unconnected-(MICROCONTROLLER-Pad42)") (class "Default")
      (node (ref "MICROCONTROLLER") (pin "42") (pinfunction "42_42") (pintype "bidirectional"))
    )
    (net (code "110") (name "unconnected-(MICROCONTROLLER-Pad43)") (class "Default")
      (node (ref "MICROCONTROLLER") (pin "43") (pinfunction "43_43") (pintype "bidirectional"))
    )
    (net (code "111") (name "unconnected-(U$5-PadNC)") (class "Default")
      (node (ref "U$5") (pin "NC") (pinfunction "NC_NC") (pintype "bidirectional"))
    )
    (net (code "112") (name "unconnected-(U$8-LBI-Pad2)") (class "Default")
      (node (ref "U$8") (pin "2") (pinfunction "LBI_2") (pintype "bidirectional"))
    )
    (net (code "113") (name "unconnected-(U$8-LBO-Pad3)") (class "Default")
      (node (ref "U$8") (pin "3") (pinfunction "LBO_3") (pintype "bidirectional"))
    )
    (net (code "114") (name "unconnected-(U$8-REF-Pad4)") (class "Default")
      (node (ref "U$8") (pin "4") (pinfunction "REF_4") (pintype "bidirectional"))
    )
  )
)
